# ActiveMoCapDeck.net
KiCad netlist of a schematic drawn in EasyEDA Pro
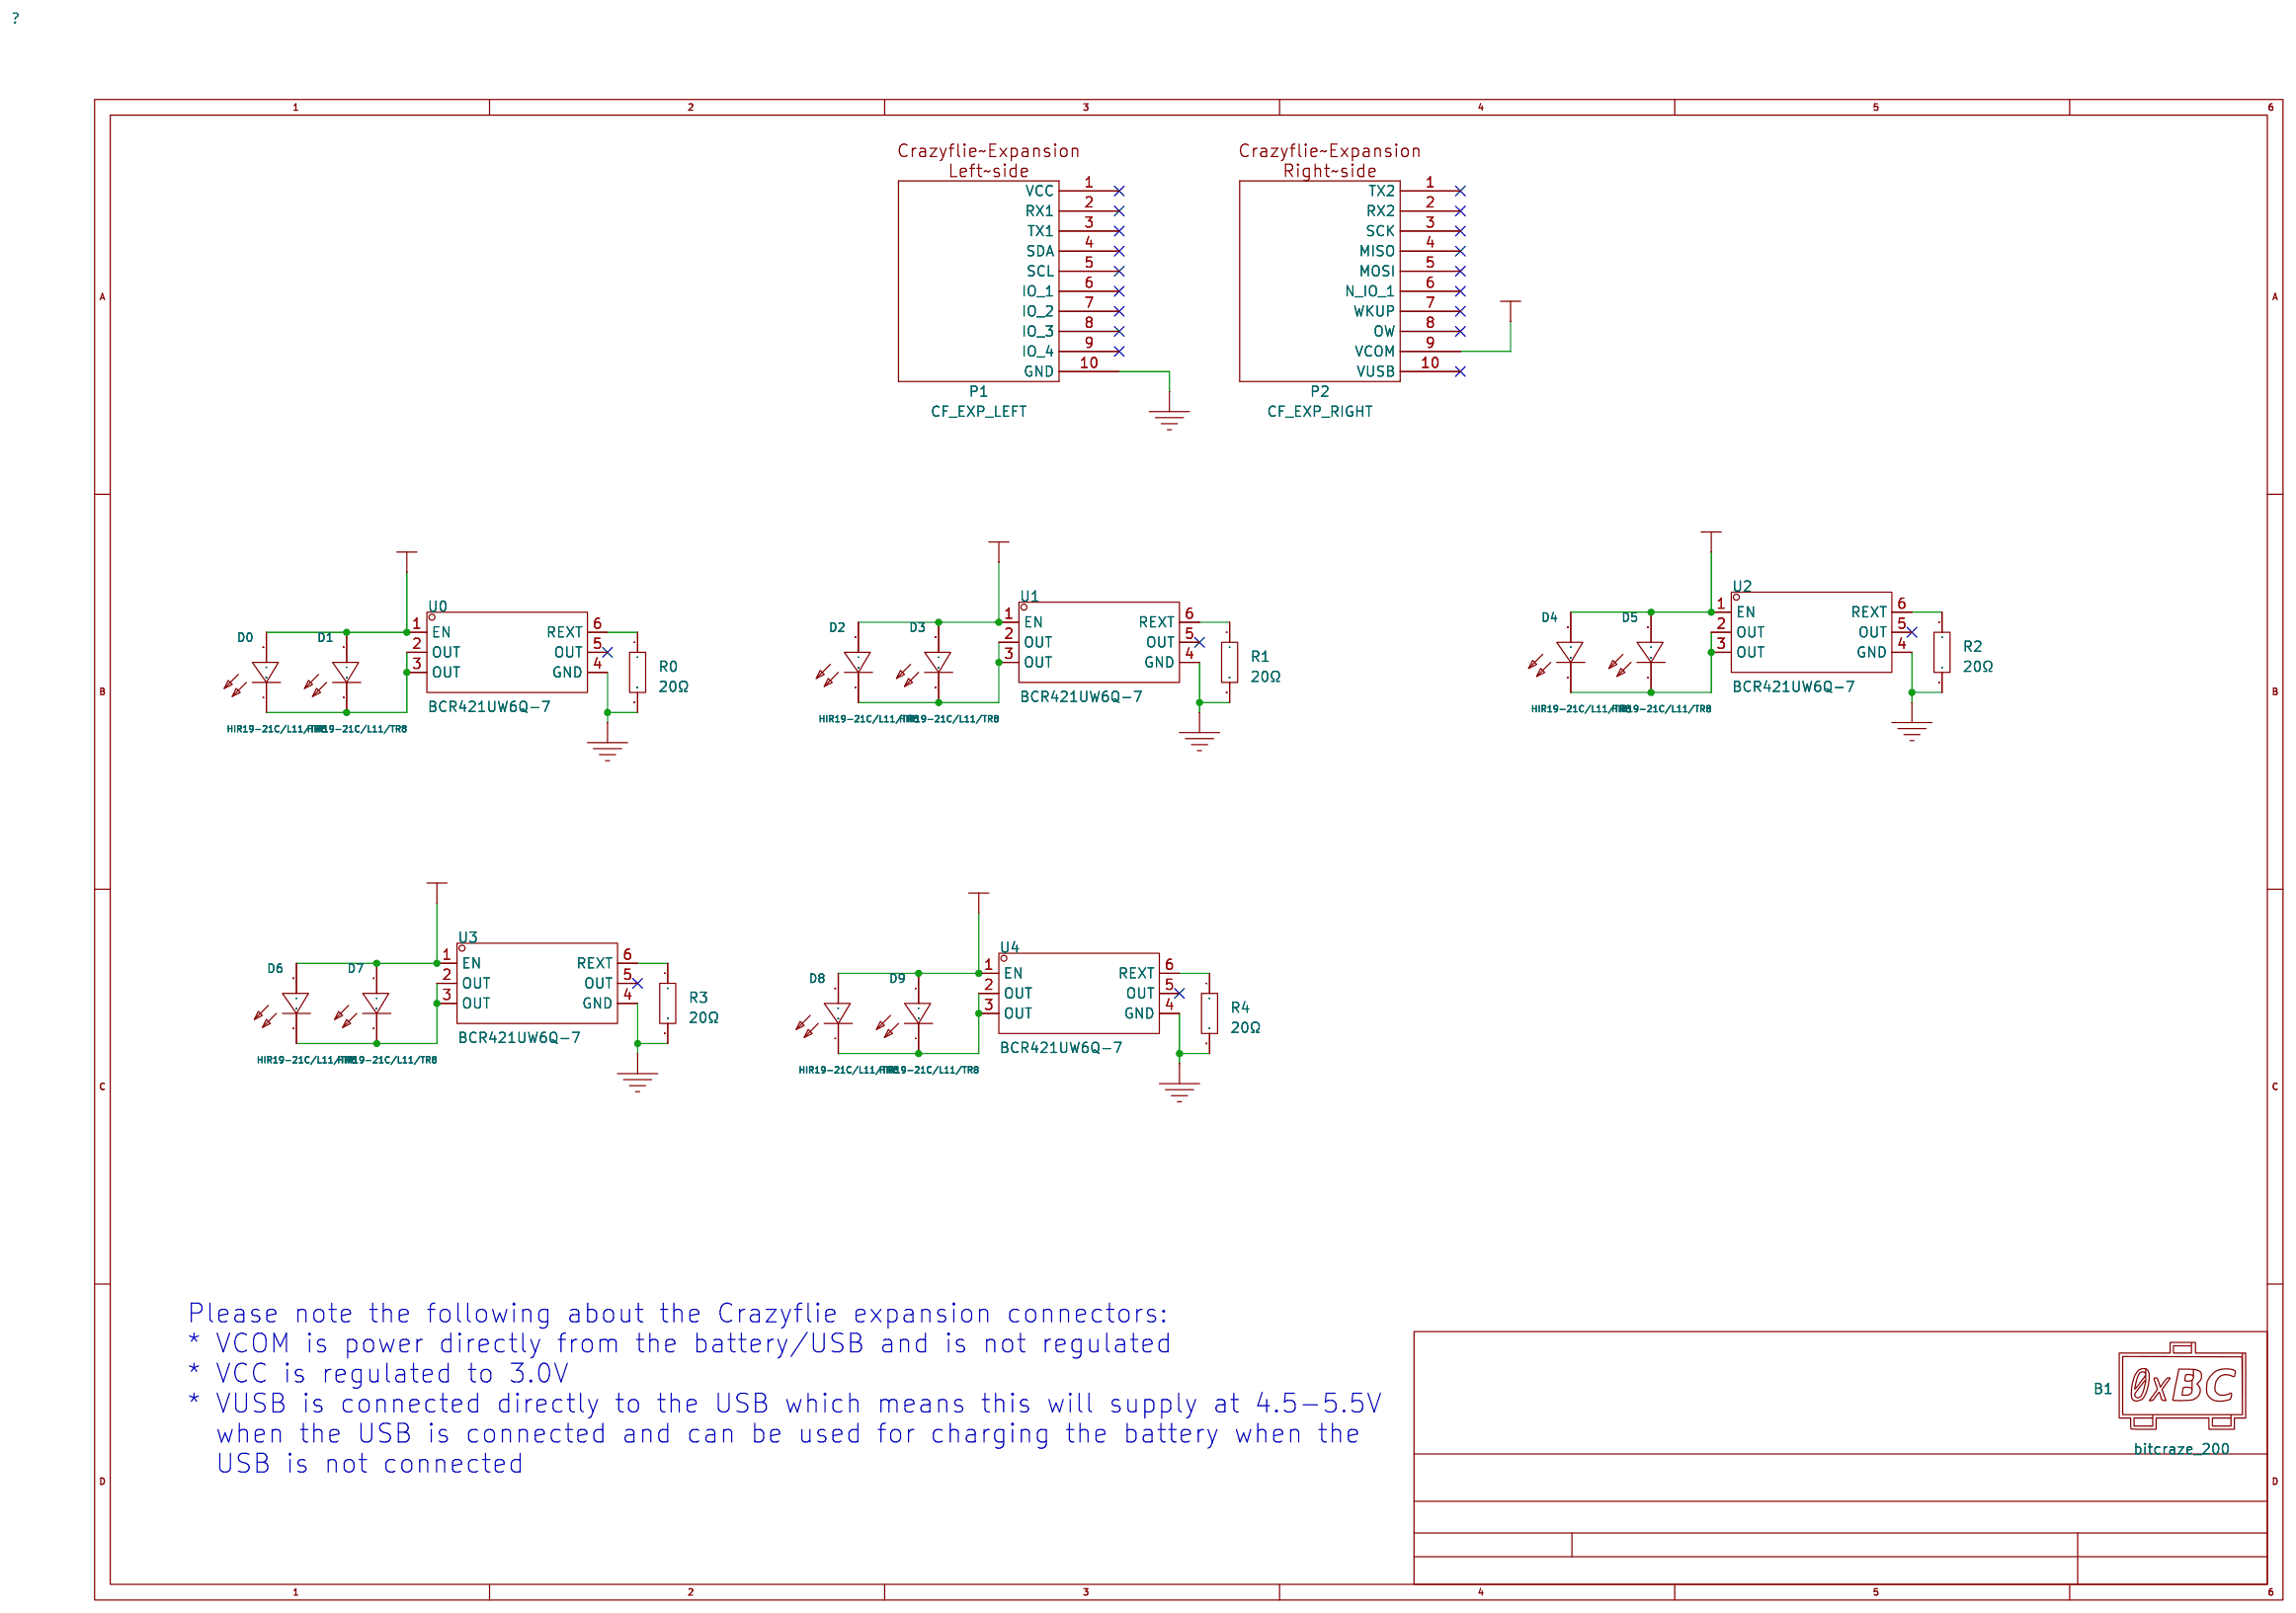
[diagram p0: schematic sheet]

(export (version "E")
  (design (tool "Eeschema 10.0.6"))
  (components
    (comp (ref "B1") (value "bitcraze_200") (libsource (lib "easyedapro") (part "bitcraze_200")))
    (comp (ref "D0")
      (value "HIR19-21C/L11/TR8")
      (footprint "easyedapro:LED0603-RD")
      (description "正向电压:1.45V;波长:850nm;辐射强度:0.2mW/sr@20mA;视角:145°;")
      (fields (field (name "Manufacturer") "EVERLIGHT(亿光)"))
      (libsource (lib "easyedapro") (part "HIR19-21C/L11/TR8"))
    )
    (comp (ref "D1")
      (value "HIR19-21C/L11/TR8")
      (footprint "easyedapro:LED0603-RD")
      (description "正向电压:1.45V;波长:850nm;辐射强度:0.2mW/sr@20mA;视角:145°;")
      (fields (field (name "Manufacturer") "EVERLIGHT(亿光)"))
      (libsource (lib "easyedapro") (part "HIR19-21C/L11/TR8"))
    )
    (comp (ref "D2")
      (value "HIR19-21C/L11/TR8")
      (footprint "easyedapro:LED0603-RD")
      (description "正向电压:1.45V;波长:850nm;辐射强度:0.2mW/sr@20mA;视角:145°;")
      (fields (field (name "Manufacturer") "EVERLIGHT(亿光)"))
      (libsource (lib "easyedapro") (part "HIR19-21C/L11/TR8"))
    )
    (comp (ref "D3")
      (value "HIR19-21C/L11/TR8")
      (footprint "easyedapro:LED0603-RD")
      (description "正向电压:1.45V;波长:850nm;辐射强度:0.2mW/sr@20mA;视角:145°;")
      (fields (field (name "Manufacturer") "EVERLIGHT(亿光)"))
      (libsource (lib "easyedapro") (part "HIR19-21C/L11/TR8"))
    )
    (comp (ref "D4")
      (value "HIR19-21C/L11/TR8")
      (footprint "easyedapro:LED0603-RD")
      (description "正向电压:1.45V;波长:850nm;辐射强度:0.2mW/sr@20mA;视角:145°;")
      (fields (field (name "Manufacturer") "EVERLIGHT(亿光)"))
      (libsource (lib "easyedapro") (part "HIR19-21C/L11/TR8"))
    )
    (comp (ref "D5")
      (value "HIR19-21C/L11/TR8")
      (footprint "easyedapro:LED0603-RD")
      (description "正向电压:1.45V;波长:850nm;辐射强度:0.2mW/sr@20mA;视角:145°;")
      (fields (field (name "Manufacturer") "EVERLIGHT(亿光)"))
      (libsource (lib "easyedapro") (part "HIR19-21C/L11/TR8"))
    )
    (comp (ref "D6")
      (value "HIR19-21C/L11/TR8")
      (footprint "easyedapro:LED0603-RD")
      (description "正向电压:1.45V;波长:850nm;辐射强度:0.2mW/sr@20mA;视角:145°;")
      (fields (field (name "Manufacturer") "EVERLIGHT(亿光)"))
      (libsource (lib "easyedapro") (part "HIR19-21C/L11/TR8"))
    )
    (comp (ref "D7")
      (value "HIR19-21C/L11/TR8")
      (footprint "easyedapro:LED0603-RD")
      (description "正向电压:1.45V;波长:850nm;辐射强度:0.2mW/sr@20mA;视角:145°;")
      (fields (field (name "Manufacturer") "EVERLIGHT(亿光)"))
      (libsource (lib "easyedapro") (part "HIR19-21C/L11/TR8"))
    )
    (comp (ref "D8")
      (value "HIR19-21C/L11/TR8")
      (footprint "easyedapro:LED0603-RD")
      (description "正向电压:1.45V;波长:850nm;辐射强度:0.2mW/sr@20mA;视角:145°;")
      (fields (field (name "Manufacturer") "EVERLIGHT(亿光)"))
      (libsource (lib "easyedapro") (part "HIR19-21C/L11/TR8"))
    )
    (comp (ref "D9")
      (value "HIR19-21C/L11/TR8")
      (footprint "easyedapro:LED0603-RD")
      (description "正向电压:1.45V;波长:850nm;辐射强度:0.2mW/sr@20mA;视角:145°;")
      (fields (field (name "Manufacturer") "EVERLIGHT(亿光)"))
      (libsource (lib "easyedapro") (part "HIR19-21C/L11/TR8"))
    )
    (comp (ref "P1") (value "CF_EXP_LEFT") (libsource (lib "easyedapro") (part "CF_EXP_LEFT")))
    (comp (ref "P2") (value "CF_EXP_RIGHT") (libsource (lib "easyedapro") (part "CF_EXP_RIGHT")))
    (comp (ref "R0")
      (value "20Ω")
      (footprint "easyedapro:R0603")
      (description "电阻类型:厚膜电阻;阻值:20Ω;精度:±5%;功率:100mW;最大工作电压:75V;温度系数:±100ppm/°C;")
      (fields (field (name "Manufacturer Part") "RC0603JR-0720RL") (field (name "Manufacturer") "YAGEO(国巨)"))
      (libsource (lib "easyedapro") (part "RC0603JR-0720RL"))
    )
    (comp (ref "R1")
      (value "20Ω")
      (footprint "easyedapro:R0603")
      (description "电阻类型:厚膜电阻;阻值:20Ω;精度:±5%;功率:100mW;最大工作电压:75V;温度系数:±100ppm/°C;")
      (fields (field (name "Manufacturer Part") "RC0603JR-0720RL") (field (name "Manufacturer") "YAGEO(国巨)"))
      (libsource (lib "easyedapro") (part "RC0603JR-0720RL"))
    )
    (comp (ref "R2")
      (value "20Ω")
      (footprint "easyedapro:R0603")
      (description "电阻类型:厚膜电阻;阻值:20Ω;精度:±5%;功率:100mW;最大工作电压:75V;温度系数:±100ppm/°C;")
      (fields (field (name "Manufacturer Part") "RC0603JR-0720RL") (field (name "Manufacturer") "YAGEO(国巨)"))
      (libsource (lib "easyedapro") (part "RC0603JR-0720RL"))
    )
    (comp (ref "R3")
      (value "20Ω")
      (footprint "easyedapro:R0603")
      (description "电阻类型:厚膜电阻;阻值:20Ω;精度:±5%;功率:100mW;最大工作电压:75V;温度系数:±100ppm/°C;")
      (fields (field (name "Manufacturer Part") "RC0603JR-0720RL") (field (name "Manufacturer") "YAGEO(国巨)"))
      (libsource (lib "easyedapro") (part "RC0603JR-0720RL"))
    )
    (comp (ref "R4")
      (value "20Ω")
      (footprint "easyedapro:R0603")
      (description "电阻类型:厚膜电阻;阻值:20Ω;精度:±5%;功率:100mW;最大工作电压:75V;温度系数:±100ppm/°C;")
      (fields (field (name "Manufacturer Part") "RC0603JR-0720RL") (field (name "Manufacturer") "YAGEO(国巨)"))
      (libsource (lib "easyedapro") (part "RC0603JR-0720RL"))
    )
    (comp (ref "U0")
      (value "BCR421UW6Q-7")
      (footprint "easyedapro:SOT-23-6_L2.9-W1.6-P0.95-LS2.8-BR")
      (description "类型:-;输入电压:18V;开关频率:-;通道数:1;输出电压:40V;输出电流:350mA;调光:PWM;拓扑结构:-;")
      (fields (field (name "Manufacturer") "DIODES(美台)"))
      (libsource (lib "easyedapro") (part "BCR421UW6Q-7"))
    )
    (comp (ref "U1")
      (value "BCR421UW6Q-7")
      (footprint "easyedapro:SOT-23-6_L2.9-W1.6-P0.95-LS2.8-BR")
      (description "类型:-;输入电压:18V;开关频率:-;通道数:1;输出电压:40V;输出电流:350mA;调光:PWM;拓扑结构:-;")
      (fields (field (name "Manufacturer") "DIODES(美台)"))
      (libsource (lib "easyedapro") (part "BCR421UW6Q-7"))
    )
    (comp (ref "U2")
      (value "BCR421UW6Q-7")
      (footprint "easyedapro:SOT-23-6_L2.9-W1.6-P0.95-LS2.8-BR")
      (description "类型:-;输入电压:18V;开关频率:-;通道数:1;输出电压:40V;输出电流:350mA;调光:PWM;拓扑结构:-;")
      (fields (field (name "Manufacturer") "DIODES(美台)"))
      (libsource (lib "easyedapro") (part "BCR421UW6Q-7"))
    )
    (comp (ref "U3")
      (value "BCR421UW6Q-7")
      (footprint "easyedapro:SOT-23-6_L2.9-W1.6-P0.95-LS2.8-BR")
      (description "类型:-;输入电压:18V;开关频率:-;通道数:1;输出电压:40V;输出电流:350mA;调光:PWM;拓扑结构:-;")
      (fields (field (name "Manufacturer") "DIODES(美台)"))
      (libsource (lib "easyedapro") (part "BCR421UW6Q-7"))
    )
    (comp (ref "U4")
      (value "BCR421UW6Q-7")
      (footprint "easyedapro:SOT-23-6_L2.9-W1.6-P0.95-LS2.8-BR")
      (description "类型:-;输入电压:18V;开关频率:-;通道数:1;输出电压:40V;输出电流:350mA;调光:PWM;拓扑结构:-;")
      (fields (field (name "Manufacturer") "DIODES(美台)"))
      (libsource (lib "easyedapro") (part "BCR421UW6Q-7"))
    )
  )
  (nets
    (net (code "1") (name "GND") (class "Default")
      (node (ref "P1") (pin "10") (pinfunction "GND_10") (pintype "unspecified"))
      (node (ref "R0") (pin "2") (pinfunction "2_2") (pintype "input"))
      (node (ref "R1") (pin "2") (pinfunction "2_2") (pintype "input"))
      (node (ref "R2") (pin "2") (pinfunction "2_2") (pintype "input"))
      (node (ref "R3") (pin "2") (pinfunction "2_2") (pintype "input"))
      (node (ref "R4") (pin "2") (pinfunction "2_2") (pintype "input"))
      (node (ref "U0") (pin "4") (pinfunction "GND_4") (pintype "unspecified"))
      (node (ref "U1") (pin "4") (pinfunction "GND_4") (pintype "unspecified"))
      (node (ref "U2") (pin "4") (pinfunction "GND_4") (pintype "unspecified"))
      (node (ref "U3") (pin "4") (pinfunction "GND_4") (pintype "unspecified"))
      (node (ref "U4") (pin "4") (pinfunction "GND_4") (pintype "unspecified"))
    )
    (net (code "2") (name "Net-(D0-C)") (class "Default")
      (node (ref "D0") (pin "1") (pinfunction "C_1") (pintype "input"))
      (node (ref "D1") (pin "1") (pinfunction "C_1") (pintype "input"))
      (node (ref "U0") (pin "2") (pinfunction "OUT_2") (pintype "unspecified"))
      (node (ref "U0") (pin "3") (pinfunction "OUT_3") (pintype "unspecified"))
    )
    (net (code "3") (name "Net-(D2-C)") (class "Default")
      (node (ref "D2") (pin "1") (pinfunction "C_1") (pintype "input"))
      (node (ref "D3") (pin "1") (pinfunction "C_1") (pintype "input"))
      (node (ref "U1") (pin "2") (pinfunction "OUT_2") (pintype "unspecified"))
      (node (ref "U1") (pin "3") (pinfunction "OUT_3") (pintype "unspecified"))
    )
    (net (code "4") (name "Net-(D4-C)") (class "Default")
      (node (ref "D4") (pin "1") (pinfunction "C_1") (pintype "input"))
      (node (ref "D5") (pin "1") (pinfunction "C_1") (pintype "input"))
      (node (ref "U2") (pin "2") (pinfunction "OUT_2") (pintype "unspecified"))
      (node (ref "U2") (pin "3") (pinfunction "OUT_3") (pintype "unspecified"))
    )
    (net (code "5") (name "Net-(D6-C)") (class "Default")
      (node (ref "D6") (pin "1") (pinfunction "C_1") (pintype "input"))
      (node (ref "D7") (pin "1") (pinfunction "C_1") (pintype "input"))
      (node (ref "U3") (pin "2") (pinfunction "OUT_2") (pintype "unspecified"))
      (node (ref "U3") (pin "3") (pinfunction "OUT_3") (pintype "unspecified"))
    )
    (net (code "6") (name "Net-(D8-C)") (class "Default")
      (node (ref "D8") (pin "1") (pinfunction "C_1") (pintype "input"))
      (node (ref "D9") (pin "1") (pinfunction "C_1") (pintype "input"))
      (node (ref "U4") (pin "2") (pinfunction "OUT_2") (pintype "unspecified"))
      (node (ref "U4") (pin "3") (pinfunction "OUT_3") (pintype "unspecified"))
    )
    (net (code "7") (name "Net-(U0-REXT)") (class "Default")
      (node (ref "R0") (pin "1") (pinfunction "1_1") (pintype "input"))
      (node (ref "U0") (pin "6") (pinfunction "REXT_6") (pintype "unspecified"))
    )
    (net (code "8") (name "Net-(U1-REXT)") (class "Default")
      (node (ref "R1") (pin "1") (pinfunction "1_1") (pintype "input"))
      (node (ref "U1") (pin "6") (pinfunction "REXT_6") (pintype "unspecified"))
    )
    (net (code "9") (name "Net-(U2-REXT)") (class "Default")
      (node (ref "R2") (pin "1") (pinfunction "1_1") (pintype "input"))
      (node (ref "U2") (pin "6") (pinfunction "REXT_6") (pintype "unspecified"))
    )
    (net (code "10") (name "Net-(U3-REXT)") (class "Default")
      (node (ref "R3") (pin "1") (pinfunction "1_1") (pintype "input"))
      (node (ref "U3") (pin "6") (pinfunction "REXT_6") (pintype "unspecified"))
    )
    (net (code "11") (name "Net-(U4-REXT)") (class "Default")
      (node (ref "R4") (pin "1") (pinfunction "1_1") (pintype "input"))
      (node (ref "U4") (pin "6") (pinfunction "REXT_6") (pintype "unspecified"))
    )
    (net (code "12") (name "VCOM") (class "Default")
      (node (ref "D0") (pin "2") (pinfunction "A_2") (pintype "input"))
      (node (ref "D1") (pin "2") (pinfunction "A_2") (pintype "input"))
      (node (ref "D2") (pin "2") (pinfunction "A_2") (pintype "input"))
      (node (ref "D3") (pin "2") (pinfunction "A_2") (pintype "input"))
      (node (ref "D4") (pin "2") (pinfunction "A_2") (pintype "input"))
      (node (ref "D5") (pin "2") (pinfunction "A_2") (pintype "input"))
      (node (ref "D6") (pin "2") (pinfunction "A_2") (pintype "input"))
      (node (ref "D7") (pin "2") (pinfunction "A_2") (pintype "input"))
      (node (ref "D8") (pin "2") (pinfunction "A_2") (pintype "input"))
      (node (ref "D9") (pin "2") (pinfunction "A_2") (pintype "input"))
      (node (ref "P2") (pin "9") (pinfunction "VCOM_9") (pintype "unspecified"))
      (node (ref "U0") (pin "1") (pinfunction "EN_1") (pintype "unspecified"))
      (node (ref "U1") (pin "1") (pinfunction "EN_1") (pintype "unspecified"))
      (node (ref "U2") (pin "1") (pinfunction "EN_1") (pintype "unspecified"))
      (node (ref "U3") (pin "1") (pinfunction "EN_1") (pintype "unspecified"))
      (node (ref "U4") (pin "1") (pinfunction "EN_1") (pintype "unspecified"))
    )
    (net (code "13") (name "unconnected-(P1-IO_1-Pad6)") (class "Default")
      (node (ref "P1") (pin "6") (pinfunction "IO_1_6") (pintype "unspecified+no_connect"))
    )
    (net (code "14") (name "unconnected-(P1-IO_2-Pad7)") (class "Default")
      (node (ref "P1") (pin "7") (pinfunction "IO_2_7") (pintype "unspecified+no_connect"))
    )
    (net (code "15") (name "unconnected-(P1-IO_3-Pad8)") (class "Default")
      (node (ref "P1") (pin "8") (pinfunction "IO_3_8") (pintype "unspecified+no_connect"))
    )
    (net (code "16") (name "unconnected-(P1-IO_4-Pad9)") (class "Default")
      (node (ref "P1") (pin "9") (pinfunction "IO_4_9") (pintype "unspecified+no_connect"))
    )
    (net (code "17") (name "unconnected-(P1-RX1-Pad2)") (class "Default")
      (node (ref "P1") (pin "2") (pinfunction "RX1_2") (pintype "unspecified+no_connect"))
    )
    (net (code "18") (name "unconnected-(P1-SCL-Pad5)") (class "Default")
      (node (ref "P1") (pin "5") (pinfunction "SCL_5") (pintype "unspecified+no_connect"))
    )
    (net (code "19") (name "unconnected-(P1-SDA-Pad4)") (class "Default")
      (node (ref "P1") (pin "4") (pinfunction "SDA_4") (pintype "unspecified+no_connect"))
    )
    (net (code "20") (name "unconnected-(P1-TX1-Pad3)") (class "Default")
      (node (ref "P1") (pin "3") (pinfunction "TX1_3") (pintype "unspecified+no_connect"))
    )
    (net (code "21") (name "unconnected-(P1-VCC-Pad1)") (class "Default")
      (node (ref "P1") (pin "1") (pinfunction "VCC_1") (pintype "unspecified+no_connect"))
    )
    (net (code "22") (name "unconnected-(P2-MISO-Pad4)") (class "Default")
      (node (ref "P2") (pin "4") (pinfunction "MISO_4") (pintype "unspecified+no_connect"))
    )
    (net (code "23") (name "unconnected-(P2-MOSI-Pad5)") (class "Default")
      (node (ref "P2") (pin "5") (pinfunction "MOSI_5") (pintype "unspecified+no_connect"))
    )
    (net (code "24") (name "unconnected-(P2-N_IO_1-Pad6)") (class "Default")
      (node (ref "P2") (pin "6") (pinfunction "N_IO_1_6") (pintype "unspecified+no_connect"))
    )
    (net (code "25") (name "unconnected-(P2-OW-Pad8)") (class "Default")
      (node (ref "P2") (pin "8") (pinfunction "OW_8") (pintype "unspecified+no_connect"))
    )
    (net (code "26") (name "unconnected-(P2-RX2-Pad2)") (class "Default")
      (node (ref "P2") (pin "2") (pinfunction "RX2_2") (pintype "unspecified+no_connect"))
    )
    (net (code "27") (name "unconnected-(P2-SCK-Pad3)") (class "Default")
      (node (ref "P2") (pin "3") (pinfunction "SCK_3") (pintype "unspecified+no_connect"))
    )
    (net (code "28") (name "unconnected-(P2-TX2-Pad1)") (class "Default")
      (node (ref "P2") (pin "1") (pinfunction "TX2_1") (pintype "unspecified+no_connect"))
    )
    (net (code "29") (name "unconnected-(P2-VUSB-Pad10)") (class "Default")
      (node (ref "P2") (pin "10") (pinfunction "VUSB_10") (pintype "unspecified+no_connect"))
    )
    (net (code "30") (name "unconnected-(P2-WKUP-Pad7)") (class "Default")
      (node (ref "P2") (pin "7") (pinfunction "WKUP_7") (pintype "unspecified+no_connect"))
    )
    (net (code "31") (name "unconnected-(U0-OUT-Pad5)") (class "Default")
      (node (ref "U0") (pin "5") (pinfunction "OUT_5") (pintype "unspecified+no_connect"))
    )
    (net (code "32") (name "unconnected-(U1-OUT-Pad5)") (class "Default")
      (node (ref "U1") (pin "5") (pinfunction "OUT_5") (pintype "unspecified+no_connect"))
    )
    (net (code "33") (name "unconnected-(U2-OUT-Pad5)") (class "Default")
      (node (ref "U2") (pin "5") (pinfunction "OUT_5") (pintype "unspecified+no_connect"))
    )
    (net (code "34") (name "unconnected-(U3-OUT-Pad5)") (class "Default")
      (node (ref "U3") (pin "5") (pinfunction "OUT_5") (pintype "unspecified+no_connect"))
    )
    (net (code "35") (name "unconnected-(U4-OUT-Pad5)") (class "Default")
      (node (ref "U4") (pin "5") (pinfunction "OUT_5") (pintype "unspecified+no_connect"))
    )
  )
)
